# licht.net
KiCad netlist of a schematic drawn in EAGLE
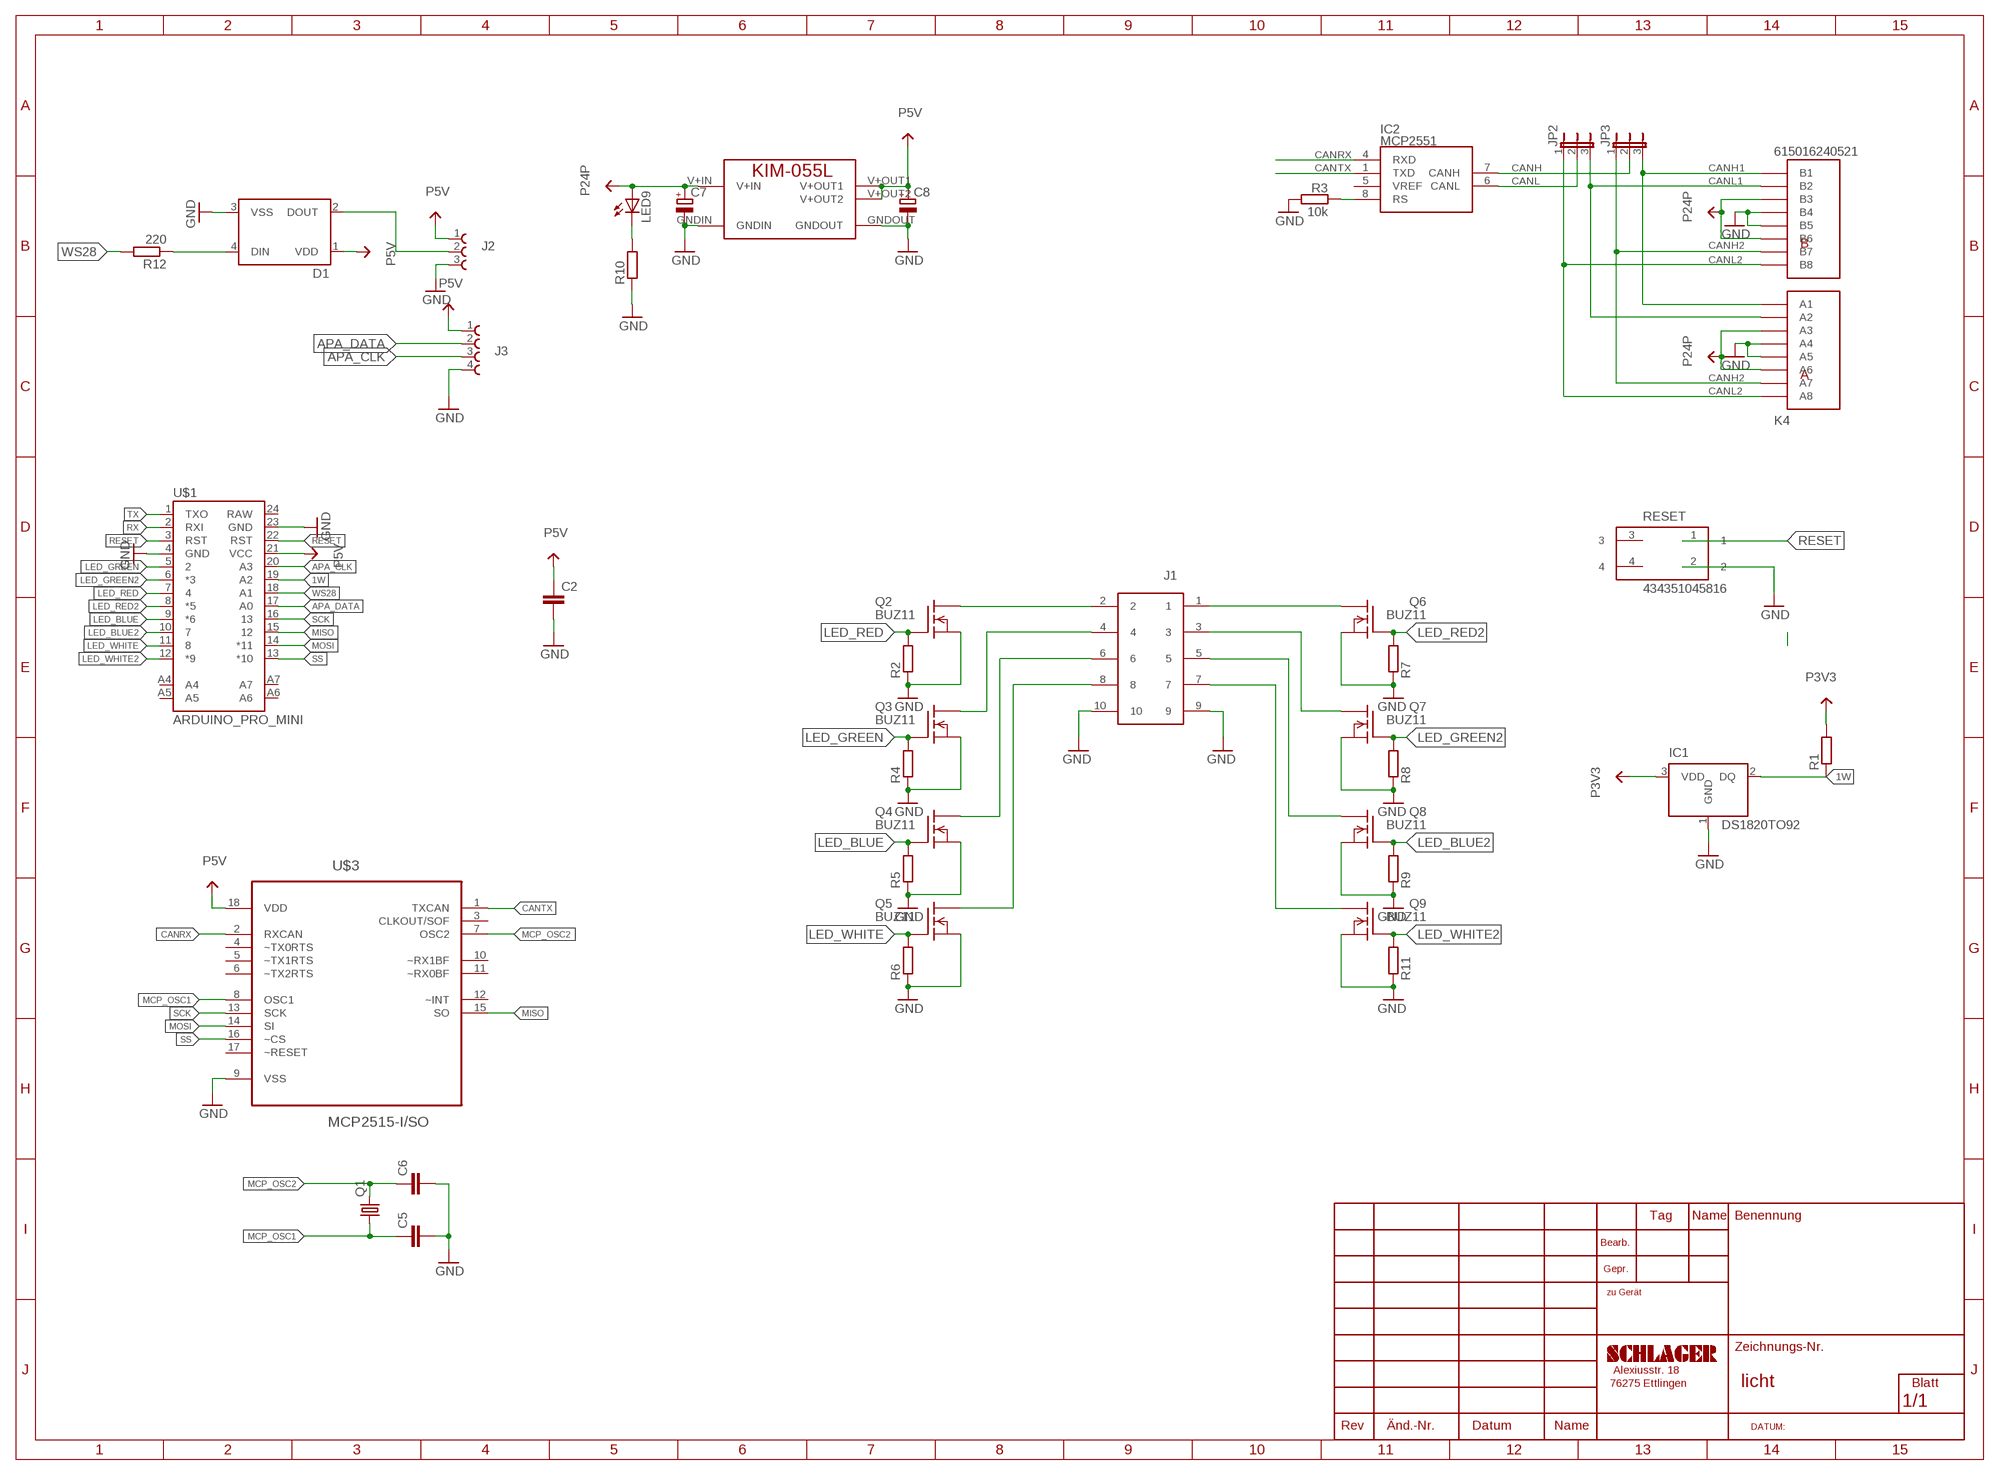
[diagram p0: schematic, sheet 1]

(export (version "E")
  (design (tool "Eeschema 10.0.6"))
  (components
    (comp (ref "C2")
      (value "C-EUC0805")
      (footprint "eagle-import:C0805")
      (libsource (lib "eagle-import") (part "C-EUC0805"))
    )
    (comp (ref "C5")
      (value "C-EUC0805")
      (footprint "eagle-import:C0805")
      (libsource (lib "eagle-import") (part "C-EUC0805"))
    )
    (comp (ref "C6")
      (value "C-EUC0805")
      (footprint "eagle-import:C0805")
      (libsource (lib "eagle-import") (part "C-EUC0805"))
    )
    (comp (ref "C7")
      (value "CPOL-EUE5-10.5")
      (footprint "eagle-import:E5-10,5")
      (libsource (lib "eagle-import") (part "CPOL-EUE5-10.5"))
    )
    (comp (ref "C8")
      (value "CPOL-EUE5-10.5")
      (footprint "eagle-import:E5-10,5")
      (libsource (lib "eagle-import") (part "CPOL-EUE5-10.5"))
    )
    (comp (ref "D1")
      (value "WS2812B")
      (footprint "eagle-import:WS2812B")
      (libsource (lib "eagle-import") (part "WS2812B"))
    )
    (comp (ref "IC1")
      (value "DS1820TO92")
      (footprint "eagle-import:TO-92")
      (libsource (lib "eagle-import") (part "DS1820TO92"))
    )
    (comp (ref "IC2")
      (value "MCP2551")
      (footprint "eagle-import:SO-8")
      (libsource (lib "eagle-import") (part "MCP2551"))
    )
    (comp (ref "J1")
      (value "691331510010")
      (footprint "eagle-import:691331510010")
      (libsource (lib "eagle-import") (part "691331510010"))
    )
    (comp (ref "J2")
      (value "691322310003")
      (footprint "eagle-import:691322310003")
      (libsource (lib "eagle-import") (part "691322310003"))
    )
    (comp (ref "J3")
      (value "691322310004")
      (footprint "eagle-import:691322310004")
      (libsource (lib "eagle-import") (part "691322310004"))
    )
    (comp (ref "JP2")
      (value "JP2E")
      (footprint "eagle-import:JP2")
      (libsource (lib "eagle-import") (part "JP2E"))
    )
    (comp (ref "JP3")
      (value "JP2E")
      (footprint "eagle-import:JP2")
      (libsource (lib "eagle-import") (part "JP2E"))
    )
    (comp (ref "K4")
      (value "615016240521")
      (footprint "eagle-import:615016240521")
      (libsource (lib "eagle-import") (part "615016240521"))
    )
    (comp (ref "LED9")
      (value "LED3MM")
      (footprint "eagle-import:LED3MM")
      (libsource (lib "eagle-import") (part "LED3MM"))
    )
    (comp (ref "MOD1")
      (value "KIM-055L")
      (footprint "eagle-import:KIM-055L")
      (libsource (lib "eagle-import") (part "KIM-055L"))
    )
    (comp (ref "Q1")
      (value "CRYSTALHC49S")
      (footprint "eagle-import:HC49_S")
      (libsource (lib "eagle-import") (part "CRYSTALHC49S"))
    )
    (comp (ref "Q2")
      (value "BUZ11")
      (footprint "eagle-import:TO220V")
      (libsource (lib "eagle-import") (part "BUZ11"))
    )
    (comp (ref "Q3")
      (value "BUZ11")
      (footprint "eagle-import:TO220V")
      (libsource (lib "eagle-import") (part "BUZ11"))
    )
    (comp (ref "Q4")
      (value "BUZ11")
      (footprint "eagle-import:TO220V")
      (libsource (lib "eagle-import") (part "BUZ11"))
    )
    (comp (ref "Q5")
      (value "BUZ11")
      (footprint "eagle-import:TO220V")
      (libsource (lib "eagle-import") (part "BUZ11"))
    )
    (comp (ref "Q6")
      (value "BUZ11")
      (footprint "eagle-import:TO220V")
      (libsource (lib "eagle-import") (part "BUZ11"))
    )
    (comp (ref "Q7")
      (value "BUZ11")
      (footprint "eagle-import:TO220V")
      (libsource (lib "eagle-import") (part "BUZ11"))
    )
    (comp (ref "Q8")
      (value "BUZ11")
      (footprint "eagle-import:TO220V")
      (libsource (lib "eagle-import") (part "BUZ11"))
    )
    (comp (ref "Q9")
      (value "BUZ11")
      (footprint "eagle-import:TO220V")
      (libsource (lib "eagle-import") (part "BUZ11"))
    )
    (comp (ref "R1")
      (value "R-EU_M0805")
      (footprint "eagle-import:M0805")
      (libsource (lib "eagle-import") (part "schlager_passiv_R-EU_M0805"))
    )
    (comp (ref "R2")
      (value "R-EU_R0805")
      (footprint "eagle-import:R0805")
      (libsource (lib "eagle-import") (part "schlager_passiv_R-EU_R0805"))
    )
    (comp (ref "R3")
      (value "10k")
      (footprint "eagle-import:R0603")
      (libsource (lib "eagle-import") (part "R-EU_R0603"))
    )
    (comp (ref "R4")
      (value "R-EU_R0805")
      (footprint "eagle-import:R0805")
      (libsource (lib "eagle-import") (part "schlager_passiv_R-EU_R0805"))
    )
    (comp (ref "R5")
      (value "R-EU_R0805")
      (footprint "eagle-import:R0805")
      (libsource (lib "eagle-import") (part "schlager_passiv_R-EU_R0805"))
    )
    (comp (ref "R6")
      (value "R-EU_R0805")
      (footprint "eagle-import:R0805")
      (libsource (lib "eagle-import") (part "schlager_passiv_R-EU_R0805"))
    )
    (comp (ref "R7")
      (value "R-EU_R0805")
      (footprint "eagle-import:R0805")
      (libsource (lib "eagle-import") (part "schlager_passiv_R-EU_R0805"))
    )
    (comp (ref "R8")
      (value "R-EU_R0805")
      (footprint "eagle-import:R0805")
      (libsource (lib "eagle-import") (part "schlager_passiv_R-EU_R0805"))
    )
    (comp (ref "R9")
      (value "R-EU_R0805")
      (footprint "eagle-import:R0805")
      (libsource (lib "eagle-import") (part "schlager_passiv_R-EU_R0805"))
    )
    (comp (ref "R10")
      (value "R-EU_R0805")
      (footprint "eagle-import:R0805")
      (libsource (lib "eagle-import") (part "schlager_passiv_R-EU_R0805"))
    )
    (comp (ref "R11")
      (value "R-EU_R0805")
      (footprint "eagle-import:R0805")
      (libsource (lib "eagle-import") (part "schlager_passiv_R-EU_R0805"))
    )
    (comp (ref "R12")
      (value "220")
      (footprint "eagle-import:R0805")
      (libsource (lib "eagle-import") (part "schlager_passiv_R-EU_R0805"))
    )
    (comp (ref "RESET")
      (value "434351045816")
      (footprint "eagle-import:434351045816")
      (libsource (lib "eagle-import") (part "434351045816"))
    )
    (comp (ref "U$1")
      (value "ARDUINO_PRO_MINI")
      (footprint "eagle-import:ARDUINO_PRO_MINI")
      (libsource (lib "eagle-import") (part "ARDUINO_PRO_MINI"))
    )
    (comp (ref "U$3")
      (value "MCP2515-I/SO")
      (footprint "eagle-import:SOIC127P1034X264-18N")
      (libsource (lib "eagle-import") (part "MCP2515-I/SO"))
    )
  )
  (nets
    (net (code "1") (name "/CANH") (class "Default")
      (node (ref "IC2") (pin "7") (pinfunction "CANH_7") (pintype "bidirectional"))
      (node (ref "JP3") (pin "2") (pinfunction "2_2") (pintype "passive"))
    )
    (net (code "2") (name "/CANH1") (class "Default")
      (node (ref "JP3") (pin "3") (pinfunction "3_3") (pintype "passive"))
      (node (ref "K4") (pin "A1") (pinfunction "A1_A1") (pintype "passive"))
      (node (ref "K4") (pin "B1") (pinfunction "B1_B1") (pintype "passive"))
    )
    (net (code "3") (name "/CANH2") (class "Default")
      (node (ref "JP3") (pin "1") (pinfunction "1_1") (pintype "passive"))
      (node (ref "K4") (pin "A7") (pinfunction "A7_A7") (pintype "passive"))
      (node (ref "K4") (pin "B7") (pinfunction "B7_B7") (pintype "passive"))
    )
    (net (code "4") (name "/CANL") (class "Default")
      (node (ref "IC2") (pin "6") (pinfunction "CANL_6") (pintype "bidirectional"))
      (node (ref "JP2") (pin "2") (pinfunction "2_2") (pintype "passive"))
    )
    (net (code "5") (name "/CANL1") (class "Default")
      (node (ref "JP2") (pin "3") (pinfunction "3_3") (pintype "passive"))
      (node (ref "K4") (pin "A2") (pinfunction "A2_A2") (pintype "passive"))
      (node (ref "K4") (pin "B2") (pinfunction "B2_B2") (pintype "passive"))
    )
    (net (code "6") (name "/CANL2") (class "Default")
      (node (ref "JP2") (pin "1") (pinfunction "1_1") (pintype "passive"))
      (node (ref "K4") (pin "A8") (pinfunction "A8_A8") (pintype "passive"))
      (node (ref "K4") (pin "B8") (pinfunction "B8_B8") (pintype "passive"))
    )
    (net (code "7") (name "1W") (class "Default")
      (node (ref "IC1") (pin "2") (pinfunction "DQ_2") (pintype "output"))
      (node (ref "R1") (pin "1") (pinfunction "1_1") (pintype "passive"))
      (node (ref "U$1") (pin "19") (pinfunction "A2_19") (pintype "bidirectional"))
    )
    (net (code "8") (name "APA_CLK") (class "Default")
      (node (ref "J3") (pin "3") (pinfunction "3_3") (pintype "passive"))
      (node (ref "U$1") (pin "20") (pinfunction "A3_20") (pintype "bidirectional"))
    )
    (net (code "9") (name "APA_DATA") (class "Default")
      (node (ref "J3") (pin "2") (pinfunction "2_2") (pintype "passive"))
      (node (ref "U$1") (pin "17") (pinfunction "A0_17") (pintype "bidirectional"))
    )
    (net (code "10") (name "CANRX") (class "Default")
      (node (ref "IC2") (pin "4") (pinfunction "RXD_4") (pintype "bidirectional"))
      (node (ref "U$3") (pin "2") (pinfunction "RXCAN_2") (pintype "input"))
    )
    (net (code "11") (name "CANTX") (class "Default")
      (node (ref "IC2") (pin "1") (pinfunction "TXD_1") (pintype "bidirectional"))
      (node (ref "U$3") (pin "1") (pinfunction "TXCAN_1") (pintype "output"))
    )
    (net (code "12") (name "GND") (class "Default")
      (node (ref "C2") (pin "2") (pinfunction "2_2") (pintype "passive"))
      (node (ref "C5") (pin "2") (pinfunction "2_2") (pintype "passive"))
      (node (ref "C6") (pin "2") (pinfunction "2_2") (pintype "passive"))
      (node (ref "C7") (pin "-") (pinfunction "-_-") (pintype "passive"))
      (node (ref "C8") (pin "-") (pinfunction "-_-") (pintype "passive"))
      (node (ref "D1") (pin "3") (pinfunction "VSS_3") (pintype "power_in"))
      (node (ref "IC1") (pin "1") (pinfunction "GND_1") (pintype "power_in"))
      (node (ref "J1") (pin "10") (pinfunction "10_10") (pintype "passive"))
      (node (ref "J1") (pin "9") (pinfunction "9_9") (pintype "passive"))
      (node (ref "J2") (pin "3") (pinfunction "3_3") (pintype "passive"))
      (node (ref "J3") (pin "4") (pinfunction "4_4") (pintype "passive"))
      (node (ref "K4") (pin "A4") (pinfunction "A4_A4") (pintype "passive"))
      (node (ref "K4") (pin "A5") (pinfunction "A5_A5") (pintype "passive"))
      (node (ref "K4") (pin "B4") (pinfunction "B4_B4") (pintype "passive"))
      (node (ref "K4") (pin "B5") (pinfunction "B5_B5") (pintype "passive"))
      (node (ref "MOD1") (pin "GNDIN") (pinfunction "GNDIN_GNDIN") (pintype "bidirectional"))
      (node (ref "MOD1") (pin "GNDOUT") (pinfunction "GNDOUT_GNDOUT") (pintype "bidirectional"))
      (node (ref "Q2") (pin "3") (pinfunction "S_3") (pintype "passive"))
      (node (ref "Q3") (pin "3") (pinfunction "S_3") (pintype "passive"))
      (node (ref "Q4") (pin "3") (pinfunction "S_3") (pintype "passive"))
      (node (ref "Q5") (pin "3") (pinfunction "S_3") (pintype "passive"))
      (node (ref "Q6") (pin "3") (pinfunction "S_3") (pintype "passive"))
      (node (ref "Q7") (pin "3") (pinfunction "S_3") (pintype "passive"))
      (node (ref "Q8") (pin "3") (pinfunction "S_3") (pintype "passive"))
      (node (ref "Q9") (pin "3") (pinfunction "S_3") (pintype "passive"))
      (node (ref "R10") (pin "1") (pinfunction "1_1") (pintype "passive"))
      (node (ref "R11") (pin "1") (pinfunction "1_1") (pintype "passive"))
      (node (ref "R2") (pin "1") (pinfunction "1_1") (pintype "passive"))
      (node (ref "R3") (pin "2") (pinfunction "2_2") (pintype "passive"))
      (node (ref "R4") (pin "1") (pinfunction "1_1") (pintype "passive"))
      (node (ref "R5") (pin "1") (pinfunction "1_1") (pintype "passive"))
      (node (ref "R6") (pin "1") (pinfunction "1_1") (pintype "passive"))
      (node (ref "R7") (pin "1") (pinfunction "1_1") (pintype "passive"))
      (node (ref "R8") (pin "1") (pinfunction "1_1") (pintype "passive"))
      (node (ref "R9") (pin "1") (pinfunction "1_1") (pintype "passive"))
      (node (ref "RESET") (pin "2") (pinfunction "2_2") (pintype "bidirectional"))
      (node (ref "U$1") (pin "23") (pinfunction "GND_23") (pintype "bidirectional"))
      (node (ref "U$1") (pin "4") (pinfunction "GND_4") (pintype "bidirectional"))
      (node (ref "U$3") (pin "9") (pinfunction "VSS_9") (pintype "power_in"))
    )
    (net (code "13") (name "LED_BLUE") (class "Default")
      (node (ref "Q4") (pin "1") (pinfunction "G_1") (pintype "passive"))
      (node (ref "R5") (pin "2") (pinfunction "2_2") (pintype "passive"))
      (node (ref "U$1") (pin "9") (pinfunction "*6_9") (pintype "bidirectional"))
    )
    (net (code "14") (name "LED_BLUE2") (class "Default")
      (node (ref "Q8") (pin "1") (pinfunction "G_1") (pintype "passive"))
      (node (ref "R9") (pin "2") (pinfunction "2_2") (pintype "passive"))
      (node (ref "U$1") (pin "10") (pinfunction "7_10") (pintype "bidirectional"))
    )
    (net (code "15") (name "LED_GREEN") (class "Default")
      (node (ref "Q3") (pin "1") (pinfunction "G_1") (pintype "passive"))
      (node (ref "R4") (pin "2") (pinfunction "2_2") (pintype "passive"))
      (node (ref "U$1") (pin "5") (pinfunction "2_5") (pintype "bidirectional"))
    )
    (net (code "16") (name "LED_GREEN2") (class "Default")
      (node (ref "Q7") (pin "1") (pinfunction "G_1") (pintype "passive"))
      (node (ref "R8") (pin "2") (pinfunction "2_2") (pintype "passive"))
      (node (ref "U$1") (pin "6") (pinfunction "*3_6") (pintype "bidirectional"))
    )
    (net (code "17") (name "LED_RED") (class "Default")
      (node (ref "Q2") (pin "1") (pinfunction "G_1") (pintype "passive"))
      (node (ref "R2") (pin "2") (pinfunction "2_2") (pintype "passive"))
      (node (ref "U$1") (pin "7") (pinfunction "4_7") (pintype "bidirectional"))
    )
    (net (code "18") (name "LED_RED2") (class "Default")
      (node (ref "Q6") (pin "1") (pinfunction "G_1") (pintype "passive"))
      (node (ref "R7") (pin "2") (pinfunction "2_2") (pintype "passive"))
      (node (ref "U$1") (pin "8") (pinfunction "*5_8") (pintype "bidirectional"))
    )
    (net (code "19") (name "LED_WHITE") (class "Default")
      (node (ref "Q5") (pin "1") (pinfunction "G_1") (pintype "passive"))
      (node (ref "R6") (pin "2") (pinfunction "2_2") (pintype "passive"))
      (node (ref "U$1") (pin "11") (pinfunction "8_11") (pintype "bidirectional"))
    )
    (net (code "20") (name "LED_WHITE2") (class "Default")
      (node (ref "Q9") (pin "1") (pinfunction "G_1") (pintype "passive"))
      (node (ref "R11") (pin "2") (pinfunction "2_2") (pintype "passive"))
      (node (ref "U$1") (pin "12") (pinfunction "*9_12") (pintype "bidirectional"))
    )
    (net (code "21") (name "MCP_OSC1") (class "Default")
      (node (ref "C5") (pin "1") (pinfunction "1_1") (pintype "passive"))
      (node (ref "Q1") (pin "1") (pinfunction "1_1") (pintype "passive"))
      (node (ref "U$3") (pin "8") (pinfunction "OSC1_8") (pintype "input"))
    )
    (net (code "22") (name "MCP_OSC2") (class "Default")
      (node (ref "C6") (pin "1") (pinfunction "1_1") (pintype "passive"))
      (node (ref "Q1") (pin "2") (pinfunction "2_2") (pintype "passive"))
      (node (ref "U$3") (pin "7") (pinfunction "OSC2_7") (pintype "output"))
    )
    (net (code "23") (name "MISO") (class "Default")
      (node (ref "U$1") (pin "15") (pinfunction "12_15") (pintype "bidirectional"))
      (node (ref "U$3") (pin "15") (pinfunction "SO_15") (pintype "output"))
    )
    (net (code "24") (name "MOSI") (class "Default")
      (node (ref "U$1") (pin "14") (pinfunction "*11_14") (pintype "bidirectional"))
      (node (ref "U$3") (pin "14") (pinfunction "SI_14") (pintype "input"))
    )
    (net (code "25") (name "Net-(D1-DIN)") (class "Default")
      (node (ref "D1") (pin "4") (pinfunction "DIN_4") (pintype "input"))
      (node (ref "R12") (pin "1") (pinfunction "1_1") (pintype "passive"))
    )
    (net (code "26") (name "Net-(D1-DOUT)") (class "Default")
      (node (ref "D1") (pin "2") (pinfunction "DOUT_2") (pintype "output"))
      (node (ref "J2") (pin "2") (pinfunction "2_2") (pintype "passive"))
    )
    (net (code "27") (name "Net-(IC2A-RS)") (class "Default")
      (node (ref "IC2") (pin "8") (pinfunction "RS_8") (pintype "bidirectional"))
      (node (ref "R3") (pin "1") (pinfunction "1_1") (pintype "passive"))
    )
    (net (code "28") (name "Net-(LED9-C)") (class "Default")
      (node (ref "LED9") (pin "K") (pinfunction "C_K") (pintype "passive"))
      (node (ref "R10") (pin "2") (pinfunction "2_2") (pintype "passive"))
    )
    (net (code "29") (name "Net-(Q2-D)") (class "Default")
      (node (ref "J1") (pin "2") (pinfunction "2_2") (pintype "passive"))
      (node (ref "Q2") (pin "2") (pinfunction "D_2") (pintype "passive"))
    )
    (net (code "30") (name "Net-(Q3-D)") (class "Default")
      (node (ref "J1") (pin "4") (pinfunction "4_4") (pintype "passive"))
      (node (ref "Q3") (pin "2") (pinfunction "D_2") (pintype "passive"))
    )
    (net (code "31") (name "Net-(Q4-D)") (class "Default")
      (node (ref "J1") (pin "6") (pinfunction "6_6") (pintype "passive"))
      (node (ref "Q4") (pin "2") (pinfunction "D_2") (pintype "passive"))
    )
    (net (code "32") (name "Net-(Q5-D)") (class "Default")
      (node (ref "J1") (pin "8") (pinfunction "8_8") (pintype "passive"))
      (node (ref "Q5") (pin "2") (pinfunction "D_2") (pintype "passive"))
    )
    (net (code "33") (name "Net-(Q6-D)") (class "Default")
      (node (ref "J1") (pin "1") (pinfunction "1_1") (pintype "passive"))
      (node (ref "Q6") (pin "2") (pinfunction "D_2") (pintype "passive"))
    )
    (net (code "34") (name "Net-(Q7-D)") (class "Default")
      (node (ref "J1") (pin "3") (pinfunction "3_3") (pintype "passive"))
      (node (ref "Q7") (pin "2") (pinfunction "D_2") (pintype "passive"))
    )
    (net (code "35") (name "Net-(Q8-D)") (class "Default")
      (node (ref "J1") (pin "5") (pinfunction "5_5") (pintype "passive"))
      (node (ref "Q8") (pin "2") (pinfunction "D_2") (pintype "passive"))
    )
    (net (code "36") (name "Net-(Q9-D)") (class "Default")
      (node (ref "J1") (pin "7") (pinfunction "7_7") (pintype "passive"))
      (node (ref "Q9") (pin "2") (pinfunction "D_2") (pintype "passive"))
    )
    (net (code "37") (name "P3V3") (class "Default")
      (node (ref "IC1") (pin "3") (pinfunction "VDD_3") (pintype "input"))
      (node (ref "R1") (pin "2") (pinfunction "2_2") (pintype "passive"))
    )
    (net (code "38") (name "P5V") (class "Default")
      (node (ref "C2") (pin "1") (pinfunction "1_1") (pintype "passive"))
      (node (ref "C8") (pin "+") (pinfunction "+_+") (pintype "passive"))
      (node (ref "D1") (pin "1") (pinfunction "VDD_1") (pintype "power_in"))
      (node (ref "J2") (pin "1") (pinfunction "1_1") (pintype "passive"))
      (node (ref "J3") (pin "1") (pinfunction "1_1") (pintype "passive"))
      (node (ref "MOD1") (pin "V+OUT1") (pinfunction "V+OUT1_V+OUT1") (pintype "bidirectional"))
      (node (ref "MOD1") (pin "V+OUT2") (pinfunction "V+OUT2_V+OUT2") (pintype "bidirectional"))
      (node (ref "U$1") (pin "21") (pinfunction "VCC_21") (pintype "bidirectional"))
      (node (ref "U$3") (pin "18") (pinfunction "VDD_18") (pintype "power_in"))
    )
    (net (code "39") (name "P24P") (class "Default")
      (node (ref "C7") (pin "+") (pinfunction "+_+") (pintype "passive"))
      (node (ref "K4") (pin "A3") (pinfunction "A3_A3") (pintype "passive"))
      (node (ref "K4") (pin "A6") (pinfunction "A6_A6") (pintype "passive"))
      (node (ref "K4") (pin "B3") (pinfunction "B3_B3") (pintype "passive"))
      (node (ref "K4") (pin "B6") (pinfunction "B6_B6") (pintype "passive"))
      (node (ref "LED9") (pin "A") (pinfunction "A_A") (pintype "passive"))
      (node (ref "MOD1") (pin "V+IN") (pinfunction "V+IN_V+IN") (pintype "bidirectional"))
    )
    (net (code "40") (name "RESET") (class "Default")
      (node (ref "RESET") (pin "1") (pinfunction "1_1") (pintype "bidirectional"))
      (node (ref "U$1") (pin "22") (pinfunction "RST_22") (pintype "bidirectional"))
      (node (ref "U$1") (pin "3") (pinfunction "RST_3") (pintype "bidirectional"))
    )
    (net (code "41") (name "RX") (class "Default")
      (node (ref "U$1") (pin "2") (pinfunction "RXI_2") (pintype "bidirectional"))
    )
    (net (code "42") (name "SCK") (class "Default")
      (node (ref "U$1") (pin "16") (pinfunction "13_16") (pintype "bidirectional"))
      (node (ref "U$3") (pin "13") (pinfunction "SCK_13") (pintype "input"))
    )
    (net (code "43") (name "SS") (class "Default")
      (node (ref "U$1") (pin "13") (pinfunction "*10_13") (pintype "bidirectional"))
      (node (ref "U$3") (pin "16") (pinfunction "~{CS}_16") (pintype "input"))
    )
    (net (code "44") (name "TX") (class "Default")
      (node (ref "U$1") (pin "1") (pinfunction "TXO_1") (pintype "bidirectional"))
    )
    (net (code "45") (name "WS28") (class "Default")
      (node (ref "R12") (pin "2") (pinfunction "2_2") (pintype "passive"))
      (node (ref "U$1") (pin "18") (pinfunction "A1_18") (pintype "bidirectional"))
    )
    (net (code "46") (name "unconnected-(IC2A-VREF-Pad5)") (class "Default")
      (node (ref "IC2") (pin "5") (pinfunction "VREF_5") (pintype "bidirectional"))
    )
    (net (code "47") (name "unconnected-(RESET-Pad3)") (class "Default")
      (node (ref "RESET") (pin "3") (pinfunction "3_3") (pintype "bidirectional"))
    )
    (net (code "48") (name "unconnected-(RESET-Pad4)") (class "Default")
      (node (ref "RESET") (pin "4") (pinfunction "4_4") (pintype "bidirectional"))
    )
    (net (code "49") (name "unconnected-(U$1-PadA4)") (class "Default")
      (node (ref "U$1") (pin "A4") (pinfunction "A4_A4") (pintype "bidirectional"))
    )
    (net (code "50") (name "unconnected-(U$1-PadA5)") (class "Default")
      (node (ref "U$1") (pin "A5") (pinfunction "A5_A5") (pintype "bidirectional"))
    )
    (net (code "51") (name "unconnected-(U$1-PadA6)") (class "Default")
      (node (ref "U$1") (pin "A6") (pinfunction "A6_A6") (pintype "bidirectional"))
    )
    (net (code "52") (name "unconnected-(U$1-PadA7)") (class "Default")
      (node (ref "U$1") (pin "A7") (pinfunction "A7_A7") (pintype "bidirectional"))
    )
    (net (code "53") (name "unconnected-(U$1-RAW-Pad24)") (class "Default")
      (node (ref "U$1") (pin "24") (pinfunction "RAW_24") (pintype "bidirectional"))
    )
    (net (code "54") (name "unconnected-(U$3-CLKOUT{slash}SOF-Pad3)") (class "Default")
      (node (ref "U$3") (pin "3") (pinfunction "CLKOUT/SOF_3") (pintype "output"))
    )
    (net (code "55") (name "unconnected-(U$3-~{INT}-Pad12)") (class "Default")
      (node (ref "U$3") (pin "12") (pinfunction "~{INT}_12") (pintype "output"))
    )
    (net (code "56") (name "unconnected-(U$3-~{RESET}-Pad17)") (class "Default")
      (node (ref "U$3") (pin "17") (pinfunction "~{RESET}_17") (pintype "input"))
    )
    (net (code "57") (name "unconnected-(U$3-~{RX0BF}-Pad11)") (class "Default")
      (node (ref "U$3") (pin "11") (pinfunction "~{RX0BF}_11") (pintype "output"))
    )
    (net (code "58") (name "unconnected-(U$3-~{RX1BF}-Pad10)") (class "Default")
      (node (ref "U$3") (pin "10") (pinfunction "~{RX1BF}_10") (pintype "output"))
    )
    (net (code "59") (name "unconnected-(U$3-~{TX0RTS}-Pad4)") (class "Default")
      (node (ref "U$3") (pin "4") (pinfunction "~{TX0RTS}_4") (pintype "input"))
    )
    (net (code "60") (name "unconnected-(U$3-~{TX1RTS}-Pad5)") (class "Default")
      (node (ref "U$3") (pin "5") (pinfunction "~{TX1RTS}_5") (pintype "input"))
    )
    (net (code "61") (name "unconnected-(U$3-~{TX2RTS}-Pad6)") (class "Default")
      (node (ref "U$3") (pin "6") (pinfunction "~{TX2RTS}_6") (pintype "input"))
    )
  )
)
